# compact.net
KiCad netlist of a schematic drawn in EAGLE
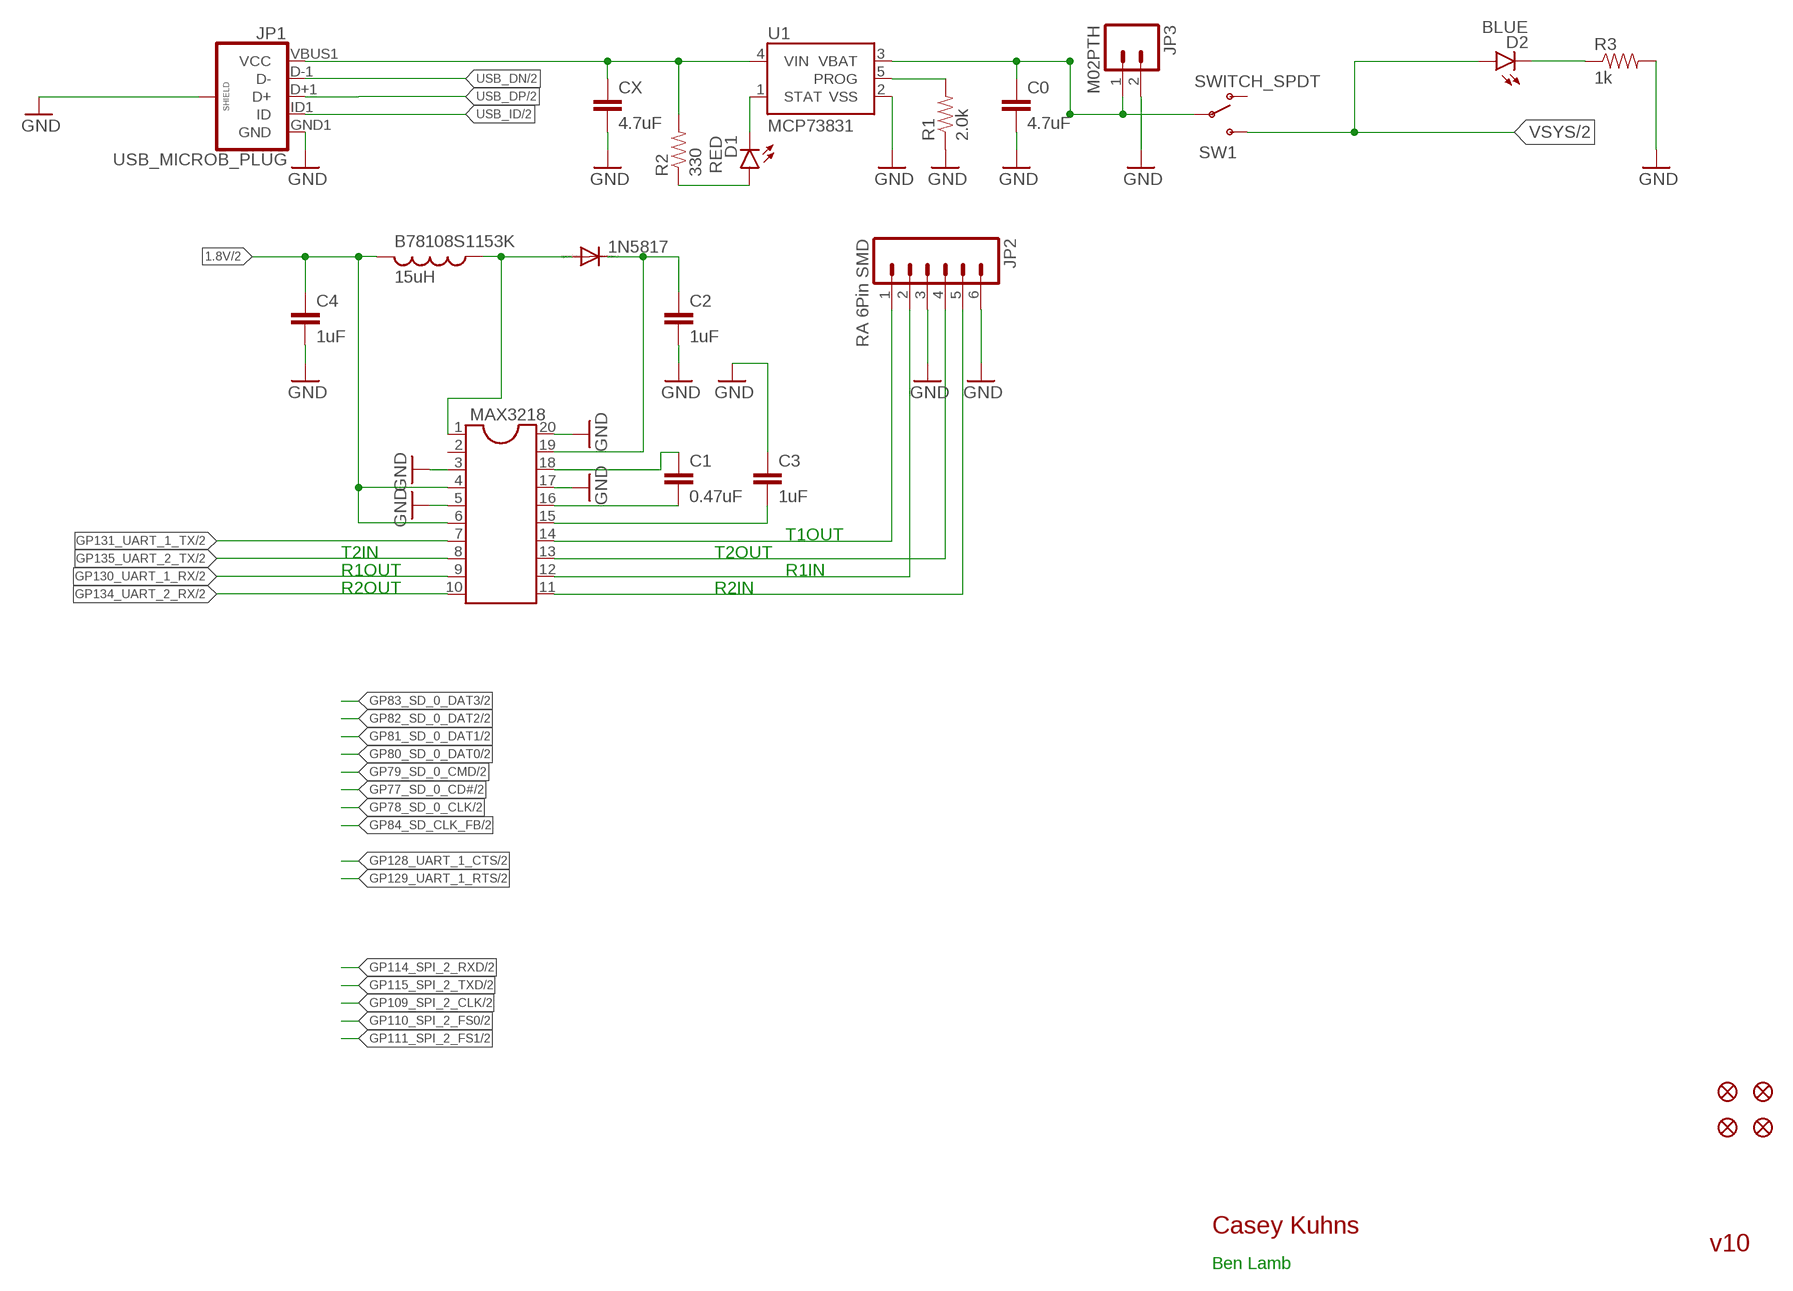
[diagram p0: schematic, sheet 1]
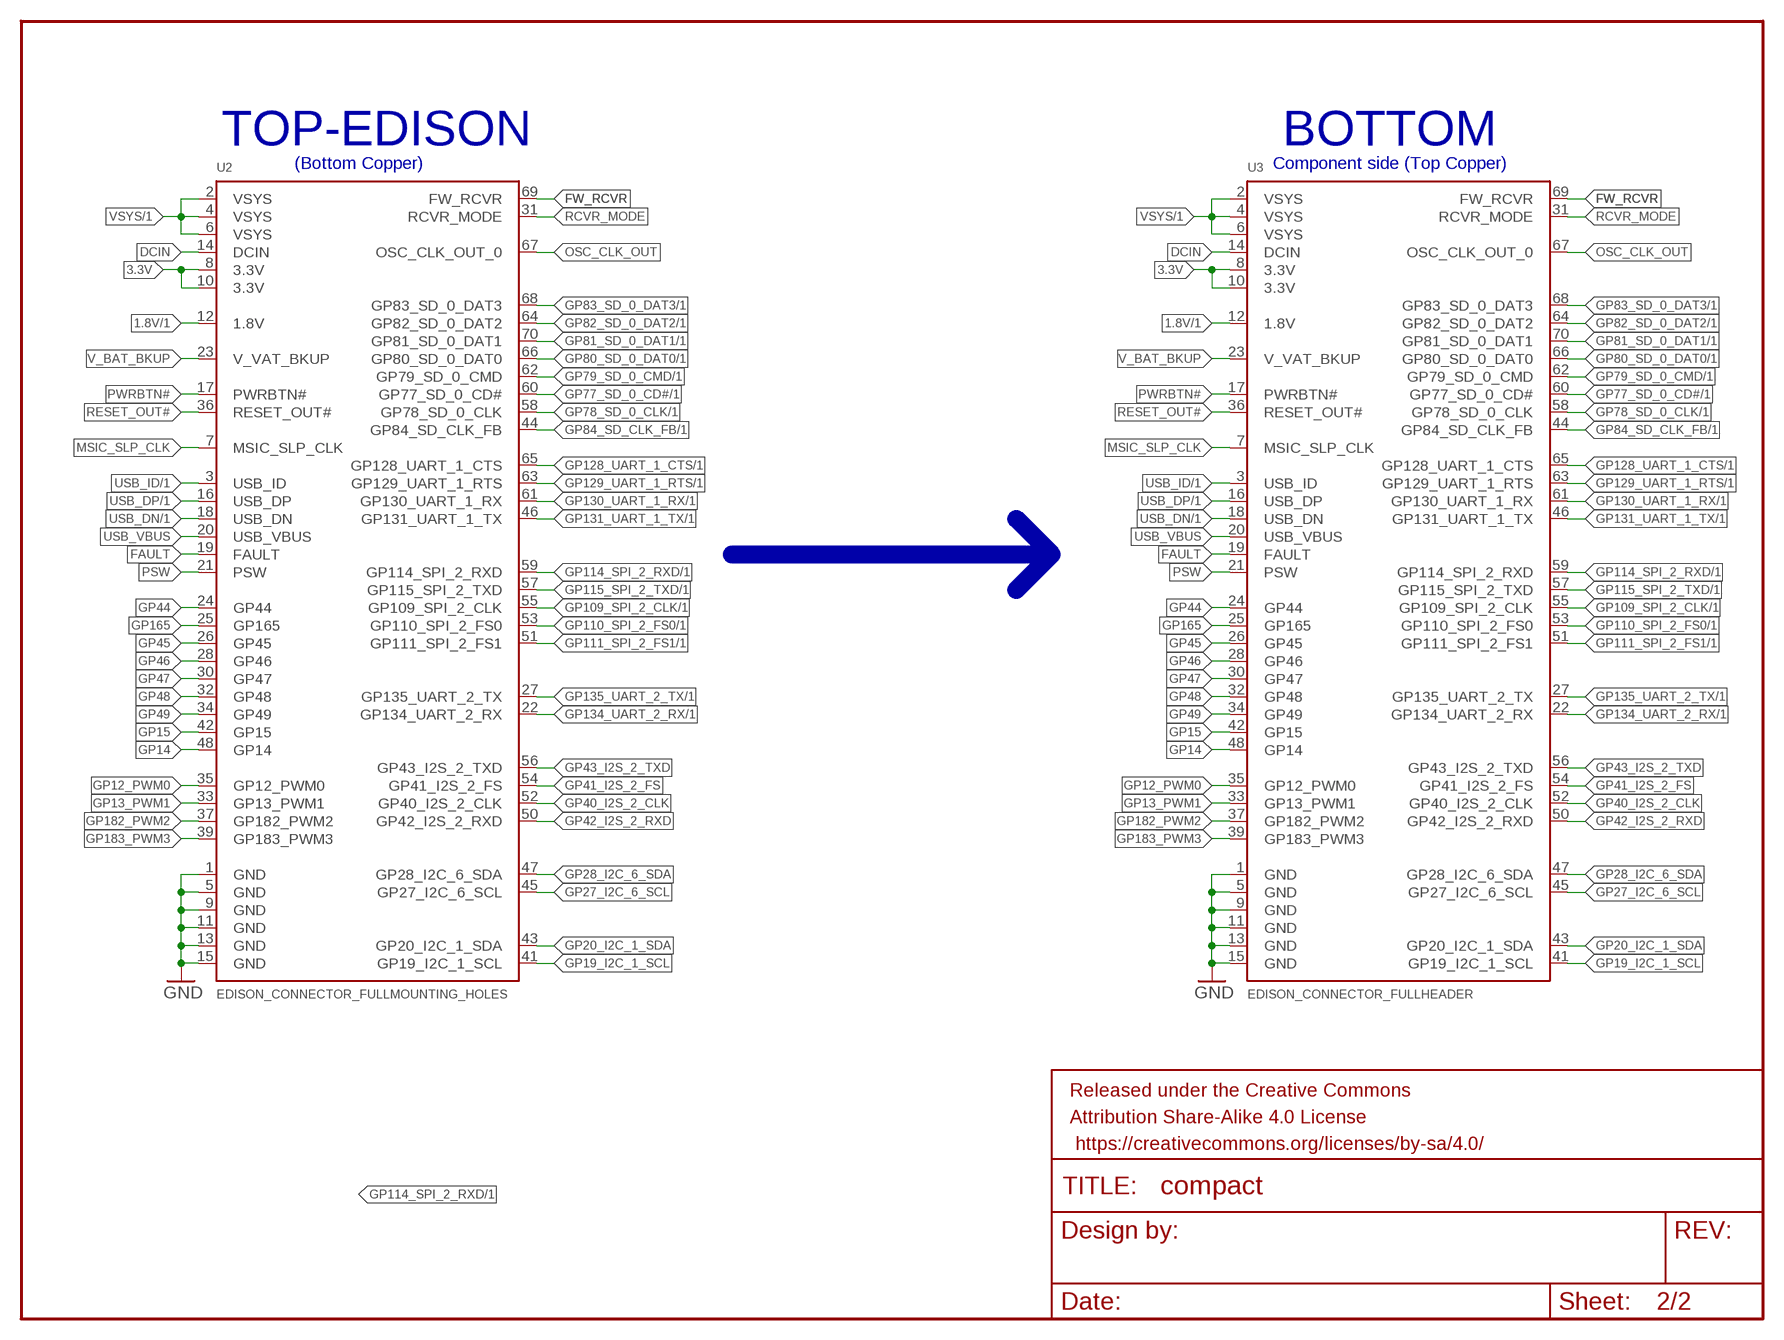
[diagram p1: schematic, sheet 2]

(export (version "E")
  (design (tool "Eeschema 10.0.6"))
  (components
    (comp (ref "1N5817")
      (value "DIODE-DO41-10")
      (footprint "eagle-import:DO41-10")
      (libsource (lib "eagle-import") (part "DIODE-DO41-10"))
    )
    (comp (ref "B78108S1153K")
      (value "15uH")
      (footprint "eagle-import:0207_15")
      (libsource (lib "eagle-import") (part "L-US0207/15"))
    )
    (comp (ref "C0")
      (value "4.7uF")
      (footprint "eagle-import:0603-CAP")
      (libsource (lib "eagle-import") (part "4.7UF-6.3V-10%(0603)0603"))
    )
    (comp (ref "C1")
      (value "0.47uF")
      (footprint "eagle-import:CAP-PTH-5MM")
      (libsource (lib "eagle-import") (part "CAPPTH1"))
    )
    (comp (ref "C2")
      (value "1uF")
      (footprint "eagle-import:CAP-PTH-5MM")
      (libsource (lib "eagle-import") (part "CAPPTH1"))
    )
    (comp (ref "C3")
      (value "1uF")
      (footprint "eagle-import:CAP-PTH-5MM")
      (libsource (lib "eagle-import") (part "CAPPTH1"))
    )
    (comp (ref "C4")
      (value "1uF")
      (footprint "eagle-import:CAP-PTH-5MM")
      (libsource (lib "eagle-import") (part "CAPPTH1"))
    )
    (comp (ref "CX")
      (value "4.7uF")
      (footprint "eagle-import:0603-CAP")
      (libsource (lib "eagle-import") (part "4.7UF-6.3V-10%(0603)0603"))
    )
    (comp (ref "D1")
      (value "RED")
      (footprint "eagle-import:LED-0603")
      (libsource (lib "eagle-import") (part "LED-RED0603"))
    )
    (comp (ref "D2")
      (value "BLUE")
      (footprint "eagle-import:LED-0603")
      (libsource (lib "eagle-import") (part "LED-BLUE0603"))
    )
    (comp (ref "FID1")
      (value "FIDUCIAL1X2")
      (footprint "eagle-import:FIDUCIAL-1X2")
      (libsource (lib "eagle-import") (part "FIDUCIAL1X2"))
    )
    (comp (ref "FID2")
      (value "FIDUCIAL1X2")
      (footprint "eagle-import:FIDUCIAL-1X2")
      (libsource (lib "eagle-import") (part "FIDUCIAL1X2"))
    )
    (comp (ref "FID3")
      (value "FIDUCIAL1X2")
      (footprint "eagle-import:FIDUCIAL-1X2")
      (libsource (lib "eagle-import") (part "FIDUCIAL1X2"))
    )
    (comp (ref "FID4")
      (value "FIDUCIAL1X2")
      (footprint "eagle-import:FIDUCIAL-1X2")
      (libsource (lib "eagle-import") (part "FIDUCIAL1X2"))
    )
    (comp (ref "JP1")
      (value "USB_MICROB_PLUG")
      (footprint "eagle-import:USB-B-MICRO-SMD_V03")
      (libsource (lib "eagle-import") (part "USB_MICROB_PLUGCONN-11752"))
    )
    (comp (ref "JP2")
      (value "RA 6Pin SMD")
      (footprint "eagle-import:1X06-SMD")
      (libsource (lib "eagle-import") (part "M06SMD"))
    )
    (comp (ref "JP3")
      (value "M02PTH")
      (footprint "eagle-import:1X02")
      (libsource (lib "eagle-import") (part "M02PTH"))
    )
    (comp (ref "MAX3218")
      (value "DIL20")
      (footprint "eagle-import:DIL20")
      (libsource (lib "eagle-import") (part "DIL20"))
    )
    (comp (ref "R1")
      (value "2.0k")
      (footprint "eagle-import:0603-RES")
      (libsource (lib "eagle-import") (part "2.0KOHM1/10W5%(0603)"))
    )
    (comp (ref "R2")
      (value "330")
      (footprint "eagle-import:0603-RES")
      (libsource (lib "eagle-import") (part "330OHM1/10W1%(0603)"))
    )
    (comp (ref "R3")
      (value "1k")
      (footprint "eagle-import:0603-RES")
      (libsource (lib "eagle-import") (part "1KOHM1/10W1%(0603)"))
    )
    (comp (ref "SW1")
      (value "SWITCH_SPDT")
      (footprint "eagle-import:KPS-1290")
      (libsource (lib "eagle-import") (part "SWITCH_SPDT"))
    )
    (comp (ref "U1")
      (value "MCP73831")
      (footprint "eagle-import:SOT23-5")
      (libsource (lib "eagle-import") (part "MCP73831"))
    )
    (comp (ref "FRAME2")
      (value "FRAME-LETTER")
      (footprint "eagle-import:CREATIVE_COMMONS")
      (libsource (lib "eagle-import") (part "FRAME-LETTER"))
    )
    (comp (ref "U2")
      (value "EDISON_CONNECTOR_FULLMOUNTING_HOLES")
      (footprint "eagle-import:EDISON_DAUGHTER")
      (libsource (lib "eagle-import") (part "EDISON_CONNECTOR_FULLMOUNTING_HOLES"))
    )
    (comp (ref "U3")
      (value "EDISON_CONNECTOR_FULLHEADER")
      (footprint "eagle-import:DF40C-70DP-0.4(51)")
      (libsource (lib "eagle-import") (part "EDISON_CONNECTOR_FULLHEADER"))
    )
  )
  (nets
    (net (code "1") (name "1.8V") (class "Default")
      (node (ref "B78108S1153K") (pin "2") (pinfunction "2_2") (pintype "passive"))
      (node (ref "C4") (pin "1") (pinfunction "1_1") (pintype "passive"))
      (node (ref "MAX3218") (pin "4") (pinfunction "4_4") (pintype "passive"))
      (node (ref "MAX3218") (pin "6") (pinfunction "6_6") (pintype "passive"))
      (node (ref "U2") (pin "12") (pinfunction "1.8V_12") (pintype "bidirectional"))
      (node (ref "U3") (pin "12") (pinfunction "1.8V_12") (pintype "bidirectional"))
    )
    (net (code "2") (name "3.3V") (class "Default")
      (node (ref "U2") (pin "10") (pinfunction "3.3V_10") (pintype "bidirectional"))
      (node (ref "U2") (pin "8") (pinfunction "3.3V_8") (pintype "bidirectional"))
      (node (ref "U3") (pin "10") (pinfunction "3.3V_10") (pintype "bidirectional"))
      (node (ref "U3") (pin "8") (pinfunction "3.3V_8") (pintype "bidirectional"))
    )
    (net (code "3") (name "DCIN") (class "Default")
      (node (ref "U2") (pin "14") (pinfunction "DCIN_14") (pintype "bidirectional"))
      (node (ref "U3") (pin "14") (pinfunction "DCIN_14") (pintype "bidirectional"))
    )
    (net (code "4") (name "FAULT") (class "Default")
      (node (ref "U2") (pin "19") (pinfunction "FAULT_19") (pintype "bidirectional"))
      (node (ref "U3") (pin "19") (pinfunction "FAULT_19") (pintype "bidirectional"))
    )
    (net (code "5") (name "FW_RCVR") (class "Default")
      (node (ref "U2") (pin "69") (pinfunction "FW_RCVR_69") (pintype "bidirectional"))
      (node (ref "U3") (pin "69") (pinfunction "FW_RCVR_69") (pintype "bidirectional"))
    )
    (net (code "6") (name "GND") (class "Default")
      (node (ref "C0") (pin "2") (pinfunction "2_2") (pintype "passive"))
      (node (ref "C2") (pin "2") (pinfunction "2_2") (pintype "passive"))
      (node (ref "C3") (pin "1") (pinfunction "1_1") (pintype "passive"))
      (node (ref "C4") (pin "2") (pinfunction "2_2") (pintype "passive"))
      (node (ref "CX") (pin "2") (pinfunction "2_2") (pintype "passive"))
      (node (ref "JP1") (pin "GND1") (pinfunction "GND_GND1") (pintype "bidirectional"))
      (node (ref "JP1") (pin "SHIELD1") (pinfunction "SHIELD_SHIELD1") (pintype "bidirectional"))
      (node (ref "JP1") (pin "SHIELD2") (pinfunction "SHIELD_SHIELD2") (pintype "bidirectional"))
      (node (ref "JP1") (pin "SHIELD3") (pinfunction "SHIELD_SHIELD3") (pintype "bidirectional"))
      (node (ref "JP2") (pin "3") (pinfunction "3_3") (pintype "passive"))
      (node (ref "JP2") (pin "6") (pinfunction "6_6") (pintype "passive"))
      (node (ref "JP3") (pin "2") (pinfunction "2_2") (pintype "passive"))
      (node (ref "MAX3218") (pin "17") (pinfunction "17_17") (pintype "passive"))
      (node (ref "MAX3218") (pin "20") (pinfunction "20_20") (pintype "passive"))
      (node (ref "MAX3218") (pin "3") (pinfunction "3_3") (pintype "passive"))
      (node (ref "MAX3218") (pin "5") (pinfunction "5_5") (pintype "passive"))
      (node (ref "R1") (pin "1") (pinfunction "1_1") (pintype "passive"))
      (node (ref "R3") (pin "2") (pinfunction "2_2") (pintype "passive"))
      (node (ref "U1") (pin "2") (pinfunction "VSS_2") (pintype "power_in"))
      (node (ref "U2") (pin "1") (pinfunction "GND_1") (pintype "bidirectional"))
      (node (ref "U2") (pin "11") (pinfunction "GND_11") (pintype "bidirectional"))
      (node (ref "U2") (pin "13") (pinfunction "GND_13") (pintype "bidirectional"))
      (node (ref "U2") (pin "15") (pinfunction "GND_15") (pintype "bidirectional"))
      (node (ref "U2") (pin "5") (pinfunction "GND_5") (pintype "bidirectional"))
      (node (ref "U2") (pin "9") (pinfunction "GND_9") (pintype "bidirectional"))
      (node (ref "U3") (pin "1") (pinfunction "GND_1") (pintype "bidirectional"))
      (node (ref "U3") (pin "11") (pinfunction "GND_11") (pintype "bidirectional"))
      (node (ref "U3") (pin "13") (pinfunction "GND_13") (pintype "bidirectional"))
      (node (ref "U3") (pin "15") (pinfunction "GND_15") (pintype "bidirectional"))
      (node (ref "U3") (pin "5") (pinfunction "GND_5") (pintype "bidirectional"))
      (node (ref "U3") (pin "9") (pinfunction "GND_9") (pintype "bidirectional"))
    )
    (net (code "7") (name "GP12_PWM0") (class "Default")
      (node (ref "U2") (pin "35") (pinfunction "GP12_PWM0_35") (pintype "bidirectional"))
      (node (ref "U3") (pin "35") (pinfunction "GP12_PWM0_35") (pintype "bidirectional"))
    )
    (net (code "8") (name "GP13_PWM1") (class "Default")
      (node (ref "U2") (pin "33") (pinfunction "GP13_PWM1_33") (pintype "bidirectional"))
      (node (ref "U3") (pin "33") (pinfunction "GP13_PWM1_33") (pintype "bidirectional"))
    )
    (net (code "9") (name "GP14") (class "Default")
      (node (ref "U2") (pin "48") (pinfunction "GP14_48") (pintype "bidirectional"))
      (node (ref "U3") (pin "48") (pinfunction "GP14_48") (pintype "bidirectional"))
    )
    (net (code "10") (name "GP15") (class "Default")
      (node (ref "U2") (pin "42") (pinfunction "GP15_42") (pintype "bidirectional"))
      (node (ref "U3") (pin "42") (pinfunction "GP15_42") (pintype "bidirectional"))
    )
    (net (code "11") (name "GP19_I2C_1_SCL") (class "Default")
      (node (ref "U2") (pin "41") (pinfunction "GP19_I2C_1_SCL_41") (pintype "bidirectional"))
      (node (ref "U3") (pin "41") (pinfunction "GP19_I2C_1_SCL_41") (pintype "bidirectional"))
    )
    (net (code "12") (name "GP20_I2C_1_SDA") (class "Default")
      (node (ref "U2") (pin "43") (pinfunction "GP20_I2C_1_SDA_43") (pintype "bidirectional"))
      (node (ref "U3") (pin "43") (pinfunction "GP20_I2C_1_SDA_43") (pintype "bidirectional"))
    )
    (net (code "13") (name "GP27_I2C_6_SCL") (class "Default")
      (node (ref "U2") (pin "45") (pinfunction "GP27_I2C_6_SCL_45") (pintype "bidirectional"))
      (node (ref "U3") (pin "45") (pinfunction "GP27_I2C_6_SCL_45") (pintype "bidirectional"))
    )
    (net (code "14") (name "GP28_I2C_6_SDA") (class "Default")
      (node (ref "U2") (pin "47") (pinfunction "GP28_I2C_6_SDA_47") (pintype "bidirectional"))
      (node (ref "U3") (pin "47") (pinfunction "GP28_I2C_6_SDA_47") (pintype "bidirectional"))
    )
    (net (code "15") (name "GP40_I2S_2_CLK") (class "Default")
      (node (ref "U2") (pin "52") (pinfunction "GP40_I2S_2_CLK_52") (pintype "bidirectional"))
      (node (ref "U3") (pin "52") (pinfunction "GP40_I2S_2_CLK_52") (pintype "bidirectional"))
    )
    (net (code "16") (name "GP41_I2S_2_FS") (class "Default")
      (node (ref "U2") (pin "54") (pinfunction "GP41_I2S_2_FS_54") (pintype "bidirectional"))
      (node (ref "U3") (pin "54") (pinfunction "GP41_I2S_2_FS_54") (pintype "bidirectional"))
    )
    (net (code "17") (name "GP42_I2S_2_RXD") (class "Default")
      (node (ref "U2") (pin "50") (pinfunction "GP42_I2S_2_RXD_50") (pintype "bidirectional"))
      (node (ref "U3") (pin "50") (pinfunction "GP42_I2S_2_RXD_50") (pintype "bidirectional"))
    )
    (net (code "18") (name "GP43_I2S_2_TXD") (class "Default")
      (node (ref "U2") (pin "56") (pinfunction "GP43_I2S_2_TXD_56") (pintype "bidirectional"))
      (node (ref "U3") (pin "56") (pinfunction "GP43_I2S_2_TXD_56") (pintype "bidirectional"))
    )
    (net (code "19") (name "GP44") (class "Default")
      (node (ref "U2") (pin "24") (pinfunction "GP44_24") (pintype "bidirectional"))
      (node (ref "U3") (pin "24") (pinfunction "GP44_24") (pintype "bidirectional"))
    )
    (net (code "20") (name "GP45") (class "Default")
      (node (ref "U2") (pin "26") (pinfunction "GP45_26") (pintype "bidirectional"))
      (node (ref "U3") (pin "26") (pinfunction "GP45_26") (pintype "bidirectional"))
    )
    (net (code "21") (name "GP46") (class "Default")
      (node (ref "U2") (pin "28") (pinfunction "GP46_28") (pintype "bidirectional"))
      (node (ref "U3") (pin "28") (pinfunction "GP46_28") (pintype "bidirectional"))
    )
    (net (code "22") (name "GP47") (class "Default")
      (node (ref "U2") (pin "30") (pinfunction "GP47_30") (pintype "bidirectional"))
      (node (ref "U3") (pin "30") (pinfunction "GP47_30") (pintype "bidirectional"))
    )
    (net (code "23") (name "GP48") (class "Default")
      (node (ref "U2") (pin "32") (pinfunction "GP48_32") (pintype "bidirectional"))
      (node (ref "U3") (pin "32") (pinfunction "GP48_32") (pintype "bidirectional"))
    )
    (net (code "24") (name "GP49") (class "Default")
      (node (ref "U2") (pin "34") (pinfunction "GP49_34") (pintype "bidirectional"))
      (node (ref "U3") (pin "34") (pinfunction "GP49_34") (pintype "bidirectional"))
    )
    (net (code "25") (name "GP77_SD_0_CD#") (class "Default")
      (node (ref "U2") (pin "60") (pinfunction "GP77_SD_0_CD#_60") (pintype "bidirectional"))
      (node (ref "U3") (pin "60") (pinfunction "GP77_SD_0_CD#_60") (pintype "bidirectional"))
    )
    (net (code "26") (name "GP78_SD_0_CLK") (class "Default")
      (node (ref "U2") (pin "58") (pinfunction "GP78_SD_0_CLK_58") (pintype "bidirectional"))
      (node (ref "U3") (pin "58") (pinfunction "GP78_SD_0_CLK_58") (pintype "bidirectional"))
    )
    (net (code "27") (name "GP79_SD_0_CMD") (class "Default")
      (node (ref "U2") (pin "62") (pinfunction "GP79_SD_0_CMD_62") (pintype "bidirectional"))
      (node (ref "U3") (pin "62") (pinfunction "GP79_SD_0_CMD_62") (pintype "bidirectional"))
    )
    (net (code "28") (name "GP80_SD_0_DAT0") (class "Default")
      (node (ref "U2") (pin "66") (pinfunction "GP80_SD_0_DAT0_66") (pintype "bidirectional"))
      (node (ref "U3") (pin "66") (pinfunction "GP80_SD_0_DAT0_66") (pintype "bidirectional"))
    )
    (net (code "29") (name "GP81_SD_0_DAT1") (class "Default")
      (node (ref "U2") (pin "70") (pinfunction "GP81_SD_0_DAT1_70") (pintype "bidirectional"))
      (node (ref "U3") (pin "70") (pinfunction "GP81_SD_0_DAT1_70") (pintype "bidirectional"))
    )
    (net (code "30") (name "GP82_SD_0_DAT2") (class "Default")
      (node (ref "U2") (pin "64") (pinfunction "GP82_SD_0_DAT2_64") (pintype "bidirectional"))
      (node (ref "U3") (pin "64") (pinfunction "GP82_SD_0_DAT2_64") (pintype "bidirectional"))
    )
    (net (code "31") (name "GP83_SD_0_DAT3") (class "Default")
      (node (ref "U2") (pin "68") (pinfunction "GP83_SD_0_DAT3_68") (pintype "bidirectional"))
      (node (ref "U3") (pin "68") (pinfunction "GP83_SD_0_DAT3_68") (pintype "bidirectional"))
    )
    (net (code "32") (name "GP84_SD_CLK_FB") (class "Default")
      (node (ref "U2") (pin "44") (pinfunction "GP84_SD_CLK_FB_44") (pintype "bidirectional"))
      (node (ref "U3") (pin "44") (pinfunction "GP84_SD_CLK_FB_44") (pintype "bidirectional"))
    )
    (net (code "33") (name "GP109_SPI_2_CLK") (class "Default")
      (node (ref "U2") (pin "55") (pinfunction "GP109_SPI_2_CLK_55") (pintype "bidirectional"))
      (node (ref "U3") (pin "55") (pinfunction "GP109_SPI_2_CLK_55") (pintype "bidirectional"))
    )
    (net (code "34") (name "GP110_SPI_2_FS0") (class "Default")
      (node (ref "U2") (pin "53") (pinfunction "GP110_SPI_2_FS0_53") (pintype "bidirectional"))
      (node (ref "U3") (pin "53") (pinfunction "GP110_SPI_2_FS0_53") (pintype "bidirectional"))
    )
    (net (code "35") (name "GP111_SPI_2_FS1") (class "Default")
      (node (ref "U2") (pin "51") (pinfunction "GP111_SPI_2_FS1_51") (pintype "bidirectional"))
      (node (ref "U3") (pin "51") (pinfunction "GP111_SPI_2_FS1_51") (pintype "bidirectional"))
    )
    (net (code "36") (name "GP114_SPI_2_RXD") (class "Default")
      (node (ref "U2") (pin "59") (pinfunction "GP114_SPI_2_RXD_59") (pintype "bidirectional"))
      (node (ref "U3") (pin "59") (pinfunction "GP114_SPI_2_RXD_59") (pintype "bidirectional"))
    )
    (net (code "37") (name "GP115_SPI_2_TXD") (class "Default")
      (node (ref "U2") (pin "57") (pinfunction "GP115_SPI_2_TXD_57") (pintype "bidirectional"))
      (node (ref "U3") (pin "57") (pinfunction "GP115_SPI_2_TXD_57") (pintype "bidirectional"))
    )
    (net (code "38") (name "GP128_UART_1_CTS") (class "Default")
      (node (ref "U2") (pin "65") (pinfunction "GP128_UART_1_CTS_65") (pintype "bidirectional"))
      (node (ref "U3") (pin "65") (pinfunction "GP128_UART_1_CTS_65") (pintype "bidirectional"))
    )
    (net (code "39") (name "GP129_UART_1_RTS") (class "Default")
      (node (ref "U2") (pin "63") (pinfunction "GP129_UART_1_RTS_63") (pintype "bidirectional"))
      (node (ref "U3") (pin "63") (pinfunction "GP129_UART_1_RTS_63") (pintype "bidirectional"))
    )
    (net (code "40") (name "GP130_UART_1_RX") (class "Default")
      (node (ref "MAX3218") (pin "9") (pinfunction "9_9") (pintype "passive"))
      (node (ref "U2") (pin "61") (pinfunction "GP130_UART_1_RX_61") (pintype "bidirectional"))
      (node (ref "U3") (pin "61") (pinfunction "GP130_UART_1_RX_61") (pintype "bidirectional"))
    )
    (net (code "41") (name "GP131_UART_1_TX") (class "Default")
      (node (ref "MAX3218") (pin "7") (pinfunction "7_7") (pintype "passive"))
      (node (ref "U2") (pin "46") (pinfunction "GP131_UART_1_TX_46") (pintype "bidirectional"))
      (node (ref "U3") (pin "46") (pinfunction "GP131_UART_1_TX_46") (pintype "bidirectional"))
    )
    (net (code "42") (name "GP134_UART_2_RX") (class "Default")
      (node (ref "MAX3218") (pin "10") (pinfunction "10_10") (pintype "passive"))
      (node (ref "U2") (pin "22") (pinfunction "GP134_UART_2_RX_22") (pintype "bidirectional"))
      (node (ref "U3") (pin "22") (pinfunction "GP134_UART_2_RX_22") (pintype "bidirectional"))
    )
    (net (code "43") (name "GP135_UART_2_TX") (class "Default")
      (node (ref "MAX3218") (pin "8") (pinfunction "8_8") (pintype "passive"))
      (node (ref "U2") (pin "27") (pinfunction "GP135_UART_2_TX_27") (pintype "bidirectional"))
      (node (ref "U3") (pin "27") (pinfunction "GP135_UART_2_TX_27") (pintype "bidirectional"))
    )
    (net (code "44") (name "GP165") (class "Default")
      (node (ref "U2") (pin "25") (pinfunction "GP165_25") (pintype "bidirectional"))
      (node (ref "U3") (pin "25") (pinfunction "GP165_25") (pintype "bidirectional"))
    )
    (net (code "45") (name "GP182_PWM2") (class "Default")
      (node (ref "U2") (pin "37") (pinfunction "GP182_PWM2_37") (pintype "bidirectional"))
      (node (ref "U3") (pin "37") (pinfunction "GP182_PWM2_37") (pintype "bidirectional"))
    )
    (net (code "46") (name "GP183_PWM3") (class "Default")
      (node (ref "U2") (pin "39") (pinfunction "GP183_PWM3_39") (pintype "bidirectional"))
      (node (ref "U3") (pin "39") (pinfunction "GP183_PWM3_39") (pintype "bidirectional"))
    )
    (net (code "47") (name "MSIC_SLP_CLK") (class "Default")
      (node (ref "U2") (pin "7") (pinfunction "MSIC_SLP_CLK_7") (pintype "bidirectional"))
      (node (ref "U3") (pin "7") (pinfunction "MSIC_SLP_CLK_7") (pintype "bidirectional"))
    )
    (net (code "48") (name "Net-(1N5817-PadA)") (class "Default")
      (node (ref "1N5817") (pin "A") (pinfunction "A_A") (pintype "passive"))
      (node (ref "B78108S1153K") (pin "1") (pinfunction "1_1") (pintype "passive"))
      (node (ref "MAX3218") (pin "1") (pinfunction "1_1") (pintype "passive"))
    )
    (net (code "49") (name "Net-(1N5817-PadC)") (class "Default")
      (node (ref "1N5817") (pin "C") (pinfunction "C_C") (pintype "passive"))
      (node (ref "C2") (pin "1") (pinfunction "1_1") (pintype "passive"))
      (node (ref "MAX3218") (pin "19") (pinfunction "19_19") (pintype "passive"))
    )
    (net (code "50") (name "Net-(C1-Pad1)") (class "Default")
      (node (ref "C1") (pin "1") (pinfunction "1_1") (pintype "passive"))
      (node (ref "MAX3218") (pin "18") (pinfunction "18_18") (pintype "passive"))
    )
    (net (code "51") (name "Net-(C1-Pad2)") (class "Default")
      (node (ref "C1") (pin "2") (pinfunction "2_2") (pintype "passive"))
      (node (ref "MAX3218") (pin "16") (pinfunction "16_16") (pintype "passive"))
    )
    (net (code "52") (name "Net-(C3-Pad2)") (class "Default")
      (node (ref "C3") (pin "2") (pinfunction "2_2") (pintype "passive"))
      (node (ref "MAX3218") (pin "15") (pinfunction "15_15") (pintype "passive"))
    )
    (net (code "53") (name "Net-(D1-PadA)") (class "Default")
      (node (ref "D1") (pin "A") (pinfunction "A_A") (pintype "passive"))
      (node (ref "R2") (pin "1") (pinfunction "1_1") (pintype "passive"))
    )
    (net (code "54") (name "Net-(D2-PadC)") (class "Default")
      (node (ref "D2") (pin "C") (pinfunction "C_C") (pintype "passive"))
      (node (ref "R3") (pin "1") (pinfunction "1_1") (pintype "passive"))
    )
    (net (code "55") (name "Net-(JP1-VCC)") (class "Default")
      (node (ref "CX") (pin "1") (pinfunction "1_1") (pintype "passive"))
      (node (ref "JP1") (pin "VBUS1") (pinfunction "VCC_VBUS1") (pintype "bidirectional"))
      (node (ref "R2") (pin "2") (pinfunction "2_2") (pintype "passive"))
      (node (ref "U1") (pin "4") (pinfunction "VIN_4") (pintype "power_in"))
    )
    (net (code "56") (name "Net-(JP2-Pad1)") (class "Default")
      (node (ref "JP2") (pin "1") (pinfunction "1_1") (pintype "passive"))
      (node (ref "MAX3218") (pin "14") (pinfunction "14_14") (pintype "passive"))
    )
    (net (code "57") (name "Net-(JP2-Pad2)") (class "Default")
      (node (ref "JP2") (pin "2") (pinfunction "2_2") (pintype "passive"))
      (node (ref "MAX3218") (pin "12") (pinfunction "12_12") (pintype "passive"))
    )
    (net (code "58") (name "Net-(JP2-Pad4)") (class "Default")
      (node (ref "JP2") (pin "4") (pinfunction "4_4") (pintype "passive"))
      (node (ref "MAX3218") (pin "13") (pinfunction "13_13") (pintype "passive"))
    )
    (net (code "59") (name "Net-(JP2-Pad5)") (class "Default")
      (node (ref "JP2") (pin "5") (pinfunction "5_5") (pintype "passive"))
      (node (ref "MAX3218") (pin "11") (pinfunction "11_11") (pintype "passive"))
    )
    (net (code "60") (name "Net-(U1-PROG)") (class "Default")
      (node (ref "R1") (pin "2") (pinfunction "2_2") (pintype "passive"))
      (node (ref "U1") (pin "5") (pinfunction "PROG_5") (pintype "input"))
    )
    (net (code "61") (name "Net-(U1-STAT)") (class "Default")
      (node (ref "D1") (pin "C") (pinfunction "C_C") (pintype "passive"))
      (node (ref "U1") (pin "1") (pinfunction "STAT_1") (pintype "output"))
    )
    (net (code "62") (name "Net-(U1-VBAT)") (class "Default")
      (node (ref "C0") (pin "1") (pinfunction "1_1") (pintype "passive"))
      (node (ref "JP3") (pin "1") (pinfunction "1_1") (pintype "passive"))
      (node (ref "SW1") (pin "P") (pinfunction "P_P") (pintype "passive"))
      (node (ref "U1") (pin "3") (pinfunction "VBAT_3") (pintype "power_in"))
    )
    (net (code "63") (name "OSC_CLK_OUT") (class "Default")
      (node (ref "U2") (pin "67") (pinfunction "OSC_CLK_OUT_0_67") (pintype "bidirectional"))
      (node (ref "U3") (pin "67") (pinfunction "OSC_CLK_OUT_0_67") (pintype "bidirectional"))
    )
    (net (code "64") (name "PSW") (class "Default")
      (node (ref "U2") (pin "21") (pinfunction "PSW_21") (pintype "bidirectional"))
      (node (ref "U3") (pin "21") (pinfunction "PSW_21") (pintype "bidirectional"))
    )
    (net (code "65") (name "PWRBTN#") (class "Default")
      (node (ref "U2") (pin "17") (pinfunction "PWRBTN#_17") (pintype "bidirectional"))
      (node (ref "U3") (pin "17") (pinfunction "PWRBTN#_17") (pintype "bidirectional"))
    )
    (net (code "66") (name "RCVR_MODE") (class "Default")
      (node (ref "U2") (pin "31") (pinfunction "RCVR_MODE_31") (pintype "bidirectional"))
      (node (ref "U3") (pin "31") (pinfunction "RCVR_MODE_31") (pintype "bidirectional"))
    )
    (net (code "67") (name "RESET_OUT#") (class "Default")
      (node (ref "U2") (pin "36") (pinfunction "RESET_OUT#_36") (pintype "bidirectional"))
      (node (ref "U3") (pin "36") (pinfunction "RESET_OUT#_36") (pintype "bidirectional"))
    )
    (net (code "68") (name "USB_DN") (class "Default")
      (node (ref "JP1") (pin "D-1") (pinfunction "D-_D-1") (pintype "bidirectional"))
      (node (ref "U2") (pin "18") (pinfunction "USB_DN_18") (pintype "bidirectional"))
      (node (ref "U3") (pin "18") (pinfunction "USB_DN_18") (pintype "bidirectional"))
    )
    (net (code "69") (name "USB_DP") (class "Default")
      (node (ref "JP1") (pin "D+1") (pinfunction "D+_D+1") (pintype "bidirectional"))
      (node (ref "U2") (pin "16") (pinfunction "USB_DP_16") (pintype "bidirectional"))
      (node (ref "U3") (pin "16") (pinfunction "USB_DP_16") (pintype "bidirectional"))
    )
    (net (code "70") (name "USB_ID") (class "Default")
      (node (ref "JP1") (pin "ID1") (pinfunction "ID_ID1") (pintype "bidirectional"))
      (node (ref "U2") (pin "3") (pinfunction "USB_ID_3") (pintype "bidirectional"))
      (node (ref "U3") (pin "3") (pinfunction "USB_ID_3") (pintype "bidirectional"))
    )
    (net (code "71") (name "USB_VBUS") (class "Default")
      (node (ref "U2") (pin "20") (pinfunction "USB_VBUS_20") (pintype "bidirectional"))
      (node (ref "U3") (pin "20") (pinfunction "USB_VBUS_20") (pintype "bidirectional"))
    )
    (net (code "72") (name "VSYS") (class "Default")
      (node (ref "D2") (pin "A") (pinfunction "A_A") (pintype "passive"))
      (node (ref "SW1") (pin "S") (pinfunction "S_S") (pintype "passive"))
      (node (ref "U2") (pin "2") (pinfunction "VSYS_2") (pintype "bidirectional"))
      (node (ref "U2") (pin "4") (pinfunction "VSYS_4") (pintype "bidirectional"))
      (node (ref "U2") (pin "6") (pinfunction "VSYS_6") (pintype "bidirectional"))
      (node (ref "U3") (pin "2") (pinfunction "VSYS_2") (pintype "bidirectional"))
      (node (ref "U3") (pin "4") (pinfunction "VSYS_4") (pintype "bidirectional"))
      (node (ref "U3") (pin "6") (pinfunction "VSYS_6") (pintype "bidirectional"))
    )
    (net (code "73") (name "V_BAT_BKUP") (class "Default")
      (node (ref "U2") (pin "23") (pinfunction "V_VAT_BKUP_23") (pintype "bidirectional"))
      (node (ref "U3") (pin "23") (pinfunction "V_VAT_BKUP_23") (pintype "bidirectional"))
    )
    (net (code "74") (name "unconnected-(MAX3218-Pad2)") (class "Default")
      (node (ref "MAX3218") (pin "2") (pinfunction "2_2") (pintype "passive"))
    )
    (net (code "75") (name "unconnected-(SW1-PadO)") (class "Default")
      (node (ref "SW1") (pin "O") (pinfunction "O_O") (pintype "passive"))
    )
  )
)
